# SPI_Encoders.net
KiCad netlist of a schematic drawn in Altium Designer
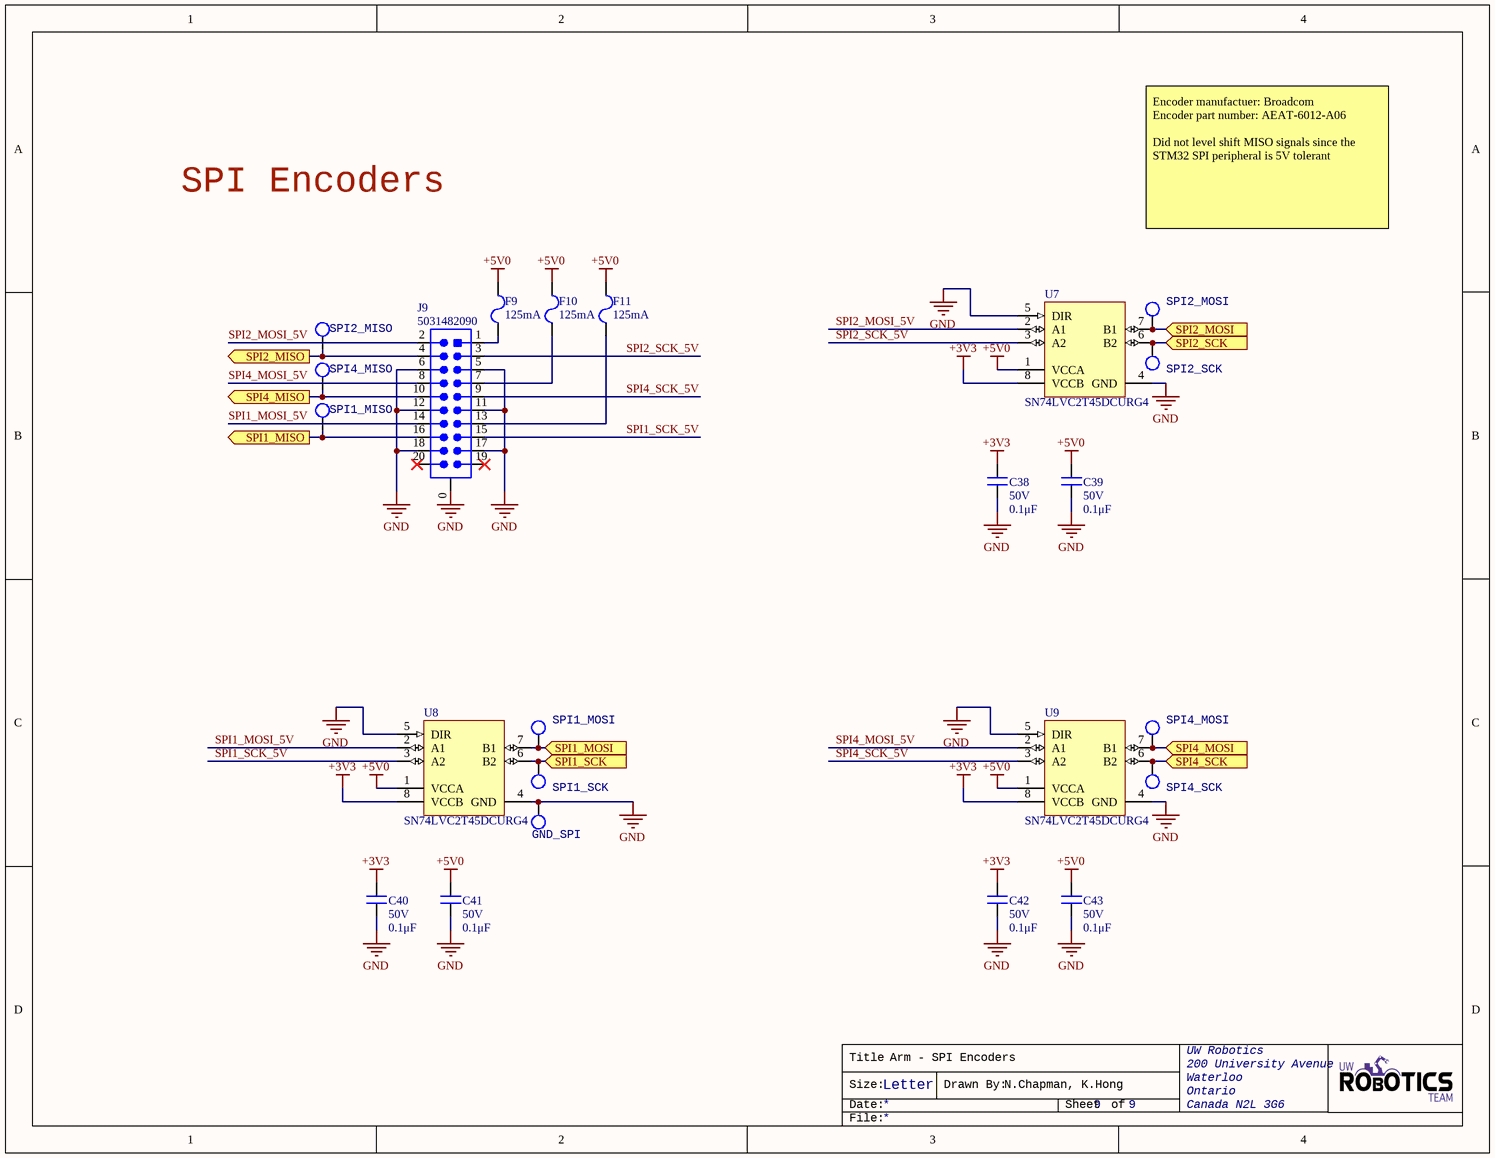
[diagram p0: SPI Encoders.SchDoc]

(export (version "E")
  (design (tool "Eeschema 10.0.6"))
  (components
    (comp (ref "C38")
      (value "0.1μF")
      (footprint "CAPC0603(1608)55_N")
      (description "CAP CER 0.1UF 50V X7R 0603")
      (fields (field (name "VOLTAGE RATING") "50V") (field (name "Comment") "CAP_0.1uF_50V_0603"))
      (libsource (lib "UWRT_Schematic_Library_2020") (part "CAP_0.1uF_50V_0603"))
    )
    (comp (ref "C39")
      (value "0.1μF")
      (footprint "CAPC0603(1608)55_N")
      (description "CAP CER 0.1UF 50V X7R 0603")
      (fields (field (name "VOLTAGE RATING") "50V") (field (name "Comment") "CAP_0.1uF_50V_0603"))
      (libsource (lib "UWRT_Schematic_Library_2020") (part "CAP_0.1uF_50V_0603"))
    )
    (comp (ref "C40")
      (value "0.1μF")
      (footprint "CAPC0603(1608)55_N")
      (description "CAP CER 0.1UF 50V X7R 0603")
      (fields (field (name "VOLTAGE RATING") "50V") (field (name "Comment") "CAP_0.1uF_50V_0603"))
      (libsource (lib "UWRT_Schematic_Library_2020") (part "CAP_0.1uF_50V_0603"))
    )
    (comp (ref "C41")
      (value "0.1μF")
      (footprint "CAPC0603(1608)55_N")
      (description "CAP CER 0.1UF 50V X7R 0603")
      (fields (field (name "VOLTAGE RATING") "50V") (field (name "Comment") "CAP_0.1uF_50V_0603"))
      (libsource (lib "UWRT_Schematic_Library_2020") (part "CAP_0.1uF_50V_0603"))
    )
    (comp (ref "C42")
      (value "0.1μF")
      (footprint "CAPC0603(1608)55_N")
      (description "CAP CER 0.1UF 50V X7R 0603")
      (fields (field (name "VOLTAGE RATING") "50V") (field (name "Comment") "CAP_0.1uF_50V_0603"))
      (libsource (lib "UWRT_Schematic_Library_2020") (part "CAP_0.1uF_50V_0603"))
    )
    (comp (ref "C43")
      (value "0.1μF")
      (footprint "CAPC0603(1608)55_N")
      (description "CAP CER 0.1UF 50V X7R 0603")
      (fields (field (name "VOLTAGE RATING") "50V") (field (name "Comment") "CAP_0.1uF_50V_0603"))
      (libsource (lib "UWRT_Schematic_Library_2020") (part "CAP_0.1uF_50V_0603"))
    )
    (comp (ref "F9")
      (value "FUSE_125mA_1206")
      (footprint "FUSE_1206")
      (description "FUSE SMD 125mA 125V")
      (fields (field (name "CURRENT RATING") "125mA"))
      (libsource (lib "UWRT_Schematic_Library_2020") (part "FUSE_125mA_1206"))
    )
    (comp (ref "F10")
      (value "FUSE_125mA_1206")
      (footprint "FUSE_1206")
      (description "FUSE SMD 125mA 125V")
      (fields (field (name "CURRENT RATING") "125mA"))
      (libsource (lib "UWRT_Schematic_Library_2020") (part "FUSE_125mA_1206"))
    )
    (comp (ref "F11")
      (value "FUSE_125mA_1206")
      (footprint "FUSE_1206")
      (description "FUSE SMD 125mA 125V")
      (fields (field (name "CURRENT RATING") "125mA"))
      (libsource (lib "UWRT_Schematic_Library_2020") (part "FUSE_125mA_1206"))
    )
    (comp (ref "GND_SPI")
      (value "TESTPOINT_LOOP")
      (footprint "TESTPOINT_LOOP")
      (description "Loop testpoint through-hole pad")
      (libsource (lib "UWRT_Schematic_Library_2020") (part "TESTPOINT_LOOP"))
    )
    (comp (ref "J9")
      (value "CON_10x2M_SM_RA")
      (footprint "MOLEX-5031482090")
      (description "CONN HEADER SMD RIGHT ANGLE 1.5MM PITCH")
      (fields (field (name "MANUFACTURER PART NUMBER 1") "5031482090"))
      (libsource (lib "UWRT_Schematic_Library_2020") (part "CON_10x2M_SM_RA"))
    )
    (comp (ref "SPI1_MISO")
      (value "TESTPOINT_LOOP")
      (footprint "TESTPOINT_LOOP")
      (description "Loop testpoint through-hole pad")
      (libsource (lib "UWRT_Schematic_Library_2020") (part "TESTPOINT_LOOP"))
    )
    (comp (ref "SPI1_MOSI")
      (value "TESTPOINT_LOOP")
      (footprint "TESTPOINT_LOOP")
      (description "Loop testpoint through-hole pad")
      (libsource (lib "UWRT_Schematic_Library_2020") (part "TESTPOINT_LOOP"))
    )
    (comp (ref "SPI1_SCK")
      (value "TESTPOINT_LOOP")
      (footprint "TESTPOINT_LOOP")
      (description "Loop testpoint through-hole pad")
      (libsource (lib "UWRT_Schematic_Library_2020") (part "TESTPOINT_LOOP"))
    )
    (comp (ref "SPI2_MISO")
      (value "TESTPOINT_LOOP")
      (footprint "TESTPOINT_LOOP")
      (description "Loop testpoint through-hole pad")
      (libsource (lib "UWRT_Schematic_Library_2020") (part "TESTPOINT_LOOP"))
    )
    (comp (ref "SPI2_MOSI")
      (value "TESTPOINT_LOOP")
      (footprint "TESTPOINT_LOOP")
      (description "Loop testpoint through-hole pad")
      (libsource (lib "UWRT_Schematic_Library_2020") (part "TESTPOINT_LOOP"))
    )
    (comp (ref "SPI2_SCK")
      (value "TESTPOINT_LOOP")
      (footprint "TESTPOINT_LOOP")
      (description "Loop testpoint through-hole pad")
      (libsource (lib "UWRT_Schematic_Library_2020") (part "TESTPOINT_LOOP"))
    )
    (comp (ref "SPI4_MISO")
      (value "TESTPOINT_LOOP")
      (footprint "TESTPOINT_LOOP")
      (description "Loop testpoint through-hole pad")
      (libsource (lib "UWRT_Schematic_Library_2020") (part "TESTPOINT_LOOP"))
    )
    (comp (ref "SPI4_MOSI")
      (value "TESTPOINT_LOOP")
      (footprint "TESTPOINT_LOOP")
      (description "Loop testpoint through-hole pad")
      (libsource (lib "UWRT_Schematic_Library_2020") (part "TESTPOINT_LOOP"))
    )
    (comp (ref "SPI4_SCK")
      (value "TESTPOINT_LOOP")
      (footprint "TESTPOINT_LOOP")
      (description "Loop testpoint through-hole pad")
      (libsource (lib "UWRT_Schematic_Library_2020") (part "TESTPOINT_LOOP"))
    )
    (comp (ref "U7")
      (value "SN74LVC2T45DCURG4")
      (footprint "DCU0008A_L")
      (fields
        (field (name "MANUFACTURER") "Texas Instruments")
        (field (name "GENERIC PART NUMBER") "SN74LVC2T45")
      )
      (libsource (lib "Altium Content Vault") (part "TI-SN74XVC2T45-8"))
    )
    (comp (ref "U8")
      (value "SN74LVC2T45DCURG4")
      (footprint "DCU0008A_L")
      (fields
        (field (name "MANUFACTURER") "Texas Instruments")
        (field (name "GENERIC PART NUMBER") "SN74LVC2T45")
      )
      (libsource (lib "Altium Content Vault") (part "TI-SN74XVC2T45-8"))
    )
    (comp (ref "U9")
      (value "SN74LVC2T45DCURG4")
      (footprint "DCU0008A_L")
      (fields
        (field (name "MANUFACTURER") "Texas Instruments")
        (field (name "GENERIC PART NUMBER") "SN74LVC2T45")
      )
      (libsource (lib "Altium Content Vault") (part "TI-SN74XVC2T45-8"))
    )
  )
  (nets
    (net (code "1") (name "+3V3") (class "Default")
      (node (ref "C38") (pin "2") (pinfunction "2_2") (pintype "passive"))
      (node (ref "C40") (pin "2") (pinfunction "2_2") (pintype "passive"))
      (node (ref "C42") (pin "2") (pinfunction "2_2") (pintype "passive"))
      (node (ref "U7") (pin "8") (pinfunction "VCCB_8") (pintype "power_in"))
      (node (ref "U8") (pin "8") (pinfunction "VCCB_8") (pintype "power_in"))
      (node (ref "U9") (pin "8") (pinfunction "VCCB_8") (pintype "power_in"))
    )
    (net (code "2") (name "+5V0") (class "Default")
      (node (ref "C39") (pin "2") (pinfunction "2_2") (pintype "passive"))
      (node (ref "C41") (pin "2") (pinfunction "2_2") (pintype "passive"))
      (node (ref "C43") (pin "2") (pinfunction "2_2") (pintype "passive"))
      (node (ref "F10") (pin "1") (pinfunction "1_1") (pintype "passive"))
      (node (ref "F11") (pin "1") (pinfunction "1_1") (pintype "passive"))
      (node (ref "F9") (pin "1") (pinfunction "1_1") (pintype "passive"))
      (node (ref "U7") (pin "1") (pinfunction "VCCA_1") (pintype "power_in"))
      (node (ref "U8") (pin "1") (pinfunction "VCCA_1") (pintype "power_in"))
      (node (ref "U9") (pin "1") (pinfunction "VCCA_1") (pintype "power_in"))
    )
    (net (code "3") (name "/SPI1_MISO") (class "Default")
      (node (ref "J9") (pin "16") (pinfunction "16_16") (pintype "passive"))
      (node (ref "SPI1_MISO") (pin "1") (pintype "passive"))
    )
    (net (code "4") (name "/SPI1_MOSI") (class "Default")
      (node (ref "SPI1_MOSI") (pin "1") (pintype "passive"))
      (node (ref "U8") (pin "7") (pinfunction "B1_7") (pintype "bidirectional"))
    )
    (net (code "5") (name "/SPI1_MOSI_5V") (class "Default")
      (node (ref "J9") (pin "14") (pinfunction "14_14") (pintype "passive"))
      (node (ref "U8") (pin "2") (pinfunction "A1_2") (pintype "bidirectional"))
    )
    (net (code "6") (name "/SPI1_SCK") (class "Default")
      (node (ref "SPI1_SCK") (pin "1") (pintype "passive"))
      (node (ref "U8") (pin "6") (pinfunction "B2_6") (pintype "bidirectional"))
    )
    (net (code "7") (name "/SPI1_SCK_5V") (class "Default")
      (node (ref "J9") (pin "15") (pinfunction "15_15") (pintype "passive"))
      (node (ref "U8") (pin "3") (pinfunction "A2_3") (pintype "bidirectional"))
    )
    (net (code "8") (name "/SPI2_MISO") (class "Default")
      (node (ref "J9") (pin "4") (pinfunction "4_4") (pintype "passive"))
      (node (ref "SPI2_MISO") (pin "1") (pintype "passive"))
    )
    (net (code "9") (name "/SPI2_MOSI") (class "Default")
      (node (ref "SPI2_MOSI") (pin "1") (pintype "passive"))
      (node (ref "U7") (pin "7") (pinfunction "B1_7") (pintype "bidirectional"))
    )
    (net (code "10") (name "/SPI2_MOSI_5V") (class "Default")
      (node (ref "J9") (pin "2") (pinfunction "2_2") (pintype "passive"))
      (node (ref "U7") (pin "2") (pinfunction "A1_2") (pintype "bidirectional"))
    )
    (net (code "11") (name "/SPI2_SCK") (class "Default")
      (node (ref "SPI2_SCK") (pin "1") (pintype "passive"))
      (node (ref "U7") (pin "6") (pinfunction "B2_6") (pintype "bidirectional"))
    )
    (net (code "12") (name "/SPI2_SCK_5V") (class "Default")
      (node (ref "J9") (pin "3") (pinfunction "3_3") (pintype "passive"))
      (node (ref "U7") (pin "3") (pinfunction "A2_3") (pintype "bidirectional"))
    )
    (net (code "13") (name "/SPI4_MISO") (class "Default")
      (node (ref "J9") (pin "10") (pinfunction "10_10") (pintype "passive"))
      (node (ref "SPI4_MISO") (pin "1") (pintype "passive"))
    )
    (net (code "14") (name "/SPI4_MOSI") (class "Default")
      (node (ref "SPI4_MOSI") (pin "1") (pintype "passive"))
      (node (ref "U9") (pin "7") (pinfunction "B1_7") (pintype "bidirectional"))
    )
    (net (code "15") (name "/SPI4_MOSI_5V") (class "Default")
      (node (ref "J9") (pin "8") (pinfunction "8_8") (pintype "passive"))
      (node (ref "U9") (pin "2") (pinfunction "A1_2") (pintype "bidirectional"))
    )
    (net (code "16") (name "/SPI4_SCK") (class "Default")
      (node (ref "SPI4_SCK") (pin "1") (pintype "passive"))
      (node (ref "U9") (pin "6") (pinfunction "B2_6") (pintype "bidirectional"))
    )
    (net (code "17") (name "/SPI4_SCK_5V") (class "Default")
      (node (ref "J9") (pin "9") (pinfunction "9_9") (pintype "passive"))
      (node (ref "U9") (pin "3") (pinfunction "A2_3") (pintype "bidirectional"))
    )
    (net (code "18") (name "GND") (class "Default")
      (node (ref "C38") (pin "1") (pinfunction "1_1") (pintype "passive"))
      (node (ref "C39") (pin "1") (pinfunction "1_1") (pintype "passive"))
      (node (ref "C40") (pin "1") (pinfunction "1_1") (pintype "passive"))
      (node (ref "C41") (pin "1") (pinfunction "1_1") (pintype "passive"))
      (node (ref "C42") (pin "1") (pinfunction "1_1") (pintype "passive"))
      (node (ref "C43") (pin "1") (pinfunction "1_1") (pintype "passive"))
      (node (ref "GND_SPI") (pin "1") (pintype "passive"))
      (node (ref "J9") (pin "0") (pinfunction "0_0") (pintype "passive"))
      (node (ref "J9") (pin "11") (pinfunction "11_11") (pintype "passive"))
      (node (ref "J9") (pin "12") (pinfunction "12_12") (pintype "passive"))
      (node (ref "J9") (pin "17") (pinfunction "17_17") (pintype "passive"))
      (node (ref "J9") (pin "18") (pinfunction "18_18") (pintype "passive"))
      (node (ref "J9") (pin "5") (pinfunction "5_5") (pintype "passive"))
      (node (ref "J9") (pin "6") (pinfunction "6_6") (pintype "passive"))
      (node (ref "U7") (pin "4") (pinfunction "GND_4") (pintype "power_in"))
      (node (ref "U7") (pin "5") (pinfunction "DIR_5") (pintype "input"))
      (node (ref "U8") (pin "4") (pinfunction "GND_4") (pintype "power_in"))
      (node (ref "U8") (pin "5") (pinfunction "DIR_5") (pintype "input"))
      (node (ref "U9") (pin "4") (pinfunction "GND_4") (pintype "power_in"))
      (node (ref "U9") (pin "5") (pinfunction "DIR_5") (pintype "input"))
    )
    (net (code "19") (name "Net-(F9-Pad2)") (class "Default")
      (node (ref "F9") (pin "2") (pinfunction "2_2") (pintype "passive"))
      (node (ref "J9") (pin "1") (pinfunction "1_1") (pintype "passive"))
    )
    (net (code "20") (name "Net-(F10-Pad2)") (class "Default")
      (node (ref "F10") (pin "2") (pinfunction "2_2") (pintype "passive"))
      (node (ref "J9") (pin "7") (pinfunction "7_7") (pintype "passive"))
    )
    (net (code "21") (name "Net-(F11-Pad2)") (class "Default")
      (node (ref "F11") (pin "2") (pinfunction "2_2") (pintype "passive"))
      (node (ref "J9") (pin "13") (pinfunction "13_13") (pintype "passive"))
    )
    (net (code "22") (name "unconnected-(J9-Pad19)") (class "Default")
      (node (ref "J9") (pin "19") (pinfunction "19_19") (pintype "passive+no_connect"))
    )
    (net (code "23") (name "unconnected-(J9-Pad20)") (class "Default")
      (node (ref "J9") (pin "20") (pinfunction "20_20") (pintype "passive+no_connect"))
    )
  )
)
